# randomcontroller.net
KiCad netlist of a schematic drawn in EAGLE
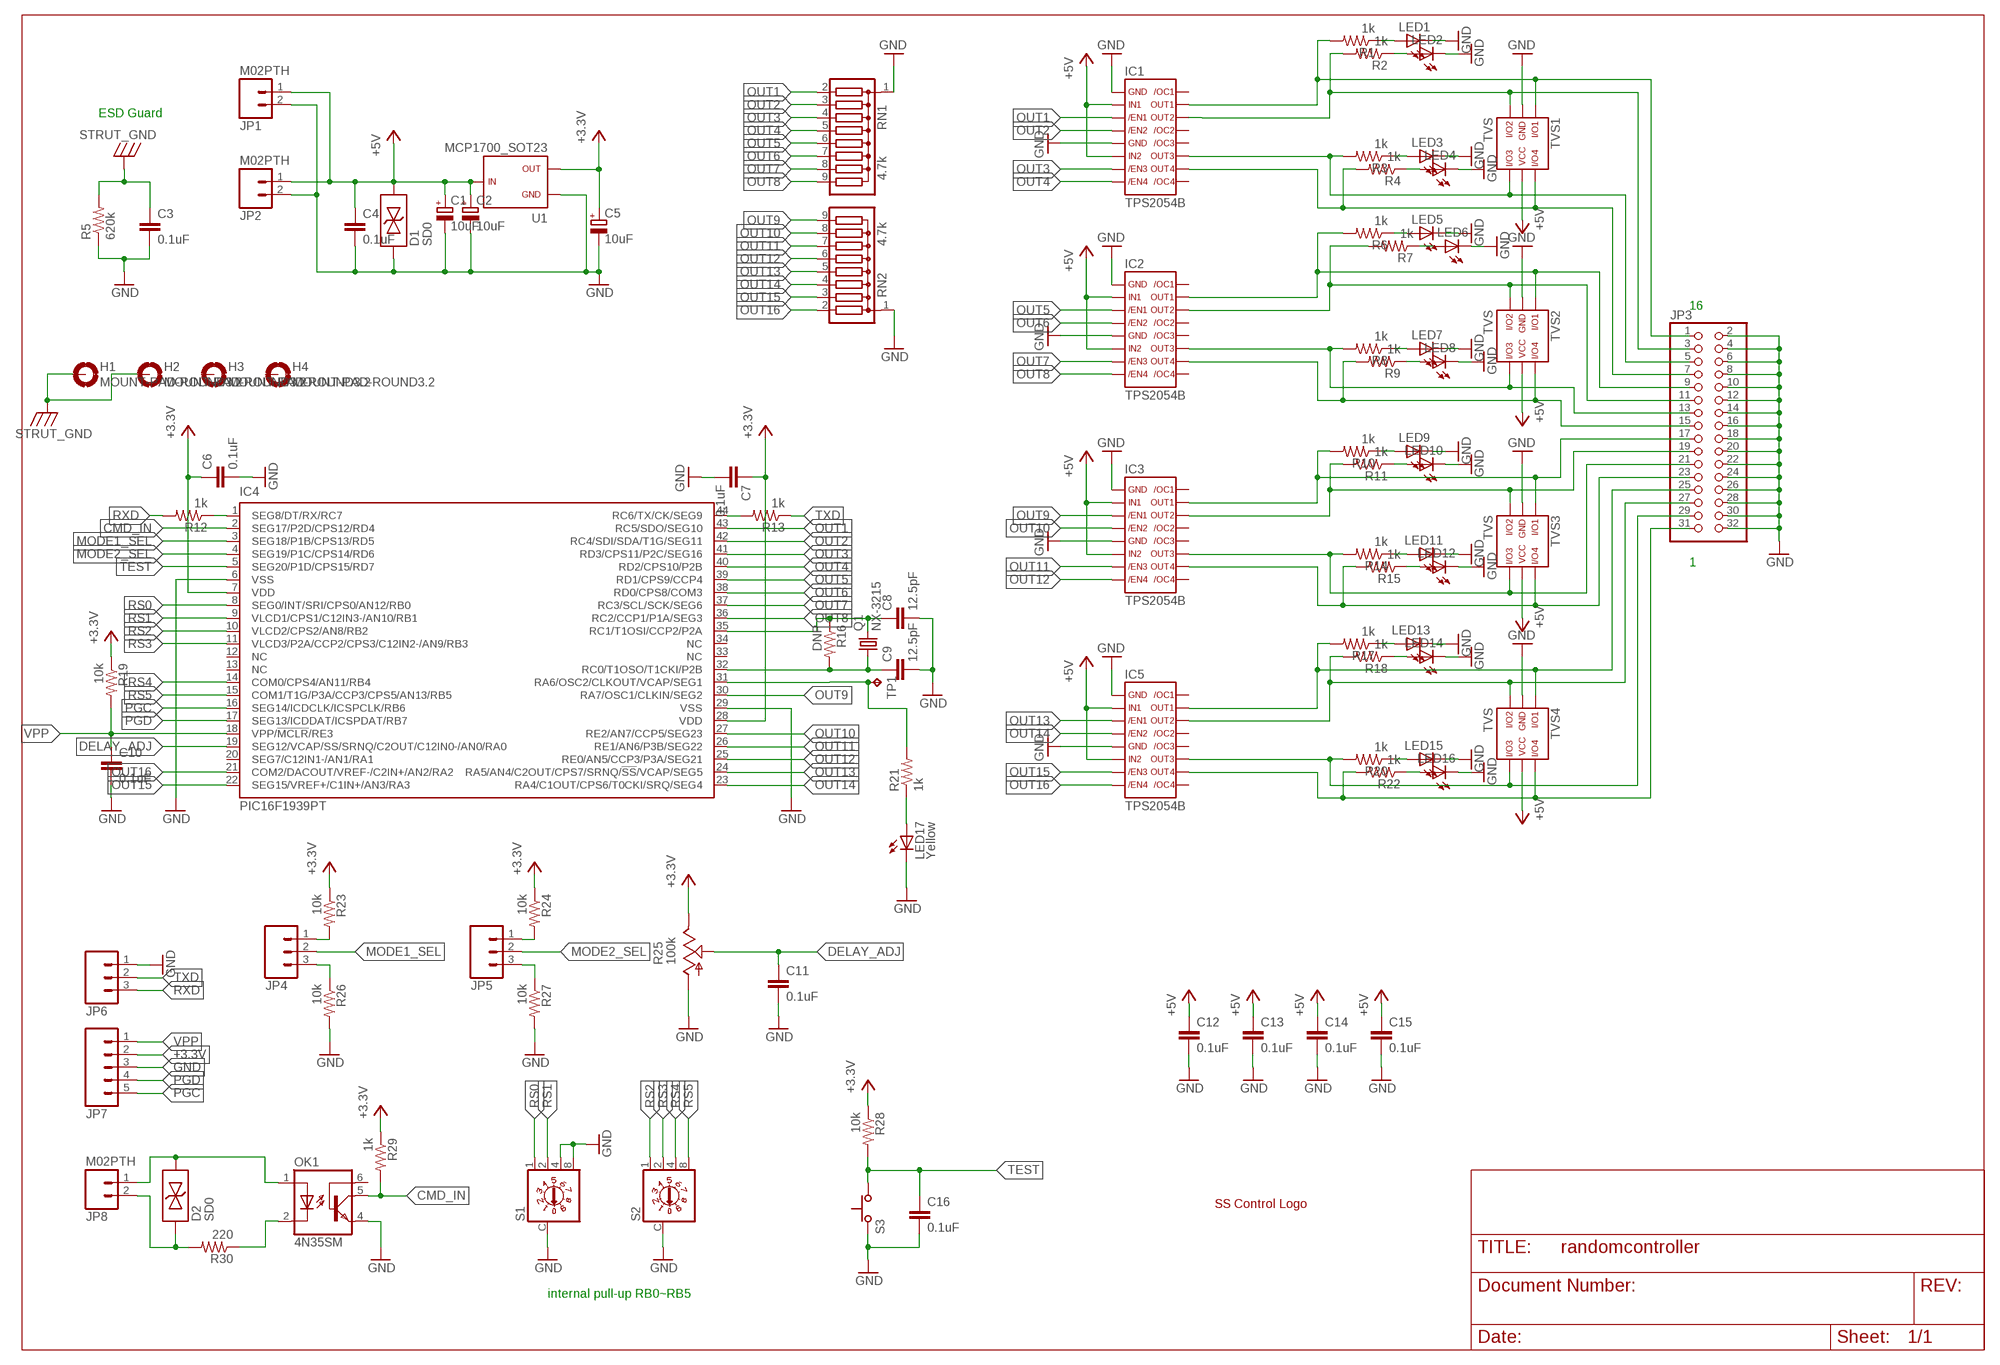
[diagram p0: schematic, sheet 1]

(export (version "E")
  (design (tool "Eeschema 10.0.6"))
  (components
    (comp (ref "C1")
      (value "10uF")
      (footprint "eagle-import:C1206(3216)-A")
      (libsource (lib "eagle-import") (part "C-TANTAL-A"))
    )
    (comp (ref "C2")
      (value "10uF")
      (footprint "eagle-import:C1206(3216)-A")
      (libsource (lib "eagle-import") (part "C-TANTAL-A"))
    )
    (comp (ref "C3")
      (value "0.1uF")
      (footprint "eagle-import:C0805(2012)")
      (libsource (lib "eagle-import") (part "C0805(2012)"))
    )
    (comp (ref "C4")
      (value "0.1uF")
      (footprint "eagle-import:C0805(2012)")
      (libsource (lib "eagle-import") (part "C0805(2012)"))
    )
    (comp (ref "C5")
      (value "10uF")
      (footprint "eagle-import:C1206(3216)-A")
      (libsource (lib "eagle-import") (part "C-TANTAL-A"))
    )
    (comp (ref "C6")
      (value "0.1uF")
      (footprint "eagle-import:C0805(2012)")
      (libsource (lib "eagle-import") (part "C0805(2012)"))
    )
    (comp (ref "C7")
      (value "0.1uF")
      (footprint "eagle-import:C0805(2012)")
      (libsource (lib "eagle-import") (part "C0805(2012)"))
    )
    (comp (ref "C8")
      (value "12.5pF")
      (footprint "eagle-import:C0805(2012)")
      (libsource (lib "eagle-import") (part "C0805(2012)"))
    )
    (comp (ref "C9")
      (value "12.5pF")
      (footprint "eagle-import:C0805(2012)")
      (libsource (lib "eagle-import") (part "C0805(2012)"))
    )
    (comp (ref "C10")
      (value "0.1uF")
      (footprint "eagle-import:C0805(2012)")
      (libsource (lib "eagle-import") (part "C0805(2012)"))
    )
    (comp (ref "C11")
      (value "0.1uF")
      (footprint "eagle-import:C0805(2012)")
      (libsource (lib "eagle-import") (part "C0805(2012)"))
    )
    (comp (ref "C12")
      (value "0.1uF")
      (footprint "eagle-import:C0805(2012)")
      (libsource (lib "eagle-import") (part "C0805(2012)"))
    )
    (comp (ref "C13")
      (value "0.1uF")
      (footprint "eagle-import:C0805(2012)")
      (libsource (lib "eagle-import") (part "C0805(2012)"))
    )
    (comp (ref "C14")
      (value "0.1uF")
      (footprint "eagle-import:C0805(2012)")
      (libsource (lib "eagle-import") (part "C0805(2012)"))
    )
    (comp (ref "C15")
      (value "0.1uF")
      (footprint "eagle-import:C0805(2012)")
      (libsource (lib "eagle-import") (part "C0805(2012)"))
    )
    (comp (ref "C16")
      (value "0.1uF")
      (footprint "eagle-import:C0805(2012)")
      (libsource (lib "eagle-import") (part "C0805(2012)"))
    )
    (comp (ref "D1")
      (value "SD0")
      (footprint "eagle-import:SOD-323")
      (libsource (lib "eagle-import") (part "SD0"))
    )
    (comp (ref "D2")
      (value "SD0")
      (footprint "eagle-import:SOD-323")
      (libsource (lib "eagle-import") (part "SD0"))
    )
    (comp (ref "H1")
      (value "MOUNT-PAD-ROUND3.2")
      (footprint "eagle-import:3,2-PAD")
      (libsource (lib "eagle-import") (part "MOUNT-PAD-ROUND3.2"))
    )
    (comp (ref "H2")
      (value "MOUNT-PAD-ROUND3.2")
      (footprint "eagle-import:3,2-PAD")
      (libsource (lib "eagle-import") (part "MOUNT-PAD-ROUND3.2"))
    )
    (comp (ref "H3")
      (value "MOUNT-PAD-ROUND3.2")
      (footprint "eagle-import:3,2-PAD")
      (libsource (lib "eagle-import") (part "MOUNT-PAD-ROUND3.2"))
    )
    (comp (ref "H4")
      (value "MOUNT-PAD-ROUND3.2")
      (footprint "eagle-import:3,2-PAD")
      (libsource (lib "eagle-import") (part "MOUNT-PAD-ROUND3.2"))
    )
    (comp (ref "IC1")
      (value "TPS2054B")
      (footprint "eagle-import:R-PDSO-G16")
      (libsource (lib "eagle-import") (part "TPS2054B"))
    )
    (comp (ref "IC2")
      (value "TPS2054B")
      (footprint "eagle-import:R-PDSO-G16")
      (libsource (lib "eagle-import") (part "TPS2054B"))
    )
    (comp (ref "IC3")
      (value "TPS2054B")
      (footprint "eagle-import:R-PDSO-G16")
      (libsource (lib "eagle-import") (part "TPS2054B"))
    )
    (comp (ref "IC4")
      (value "PIC16F1939PT")
      (footprint "eagle-import:TQFP44")
      (fields (field (name "MPN") "PIC16F1939-I/PT"))
      (libsource (lib "eagle-import") (part "PIC16F193PT9"))
    )
    (comp (ref "IC5")
      (value "TPS2054B")
      (footprint "eagle-import:R-PDSO-G16")
      (libsource (lib "eagle-import") (part "TPS2054B"))
    )
    (comp (ref "JP1")
      (value "M02PTH")
      (footprint "eagle-import:1X02")
      (libsource (lib "eagle-import") (part "M02PTH"))
    )
    (comp (ref "JP2")
      (value "M02PTH")
      (footprint "eagle-import:1X02")
      (libsource (lib "eagle-import") (part "M02PTH"))
    )
    (comp (ref "JP3")
      (value "PINHD-2X16/90")
      (footprint "eagle-import:2X16_90")
      (libsource (lib "eagle-import") (part "PINHD-2X16/90"))
    )
    (comp (ref "JP4")
      (value "M03PTH")
      (footprint "eagle-import:1X03")
      (libsource (lib "eagle-import") (part "M03PTH"))
    )
    (comp (ref "JP5")
      (value "M03PTH")
      (footprint "eagle-import:1X03")
      (libsource (lib "eagle-import") (part "M03PTH"))
    )
    (comp (ref "JP6")
      (value "M03PTH")
      (footprint "eagle-import:1X03")
      (libsource (lib "eagle-import") (part "M03PTH"))
    )
    (comp (ref "JP7")
      (value "M05PTH")
      (footprint "eagle-import:1X05")
      (libsource (lib "eagle-import") (part "M05PTH"))
    )
    (comp (ref "JP8")
      (value "M02PTH")
      (footprint "eagle-import:1X02")
      (libsource (lib "eagle-import") (part "M02PTH"))
    )
    (comp (ref "LED1")
      (value "LEDCHIPLED_0805")
      (footprint "eagle-import:CHIPLED_0805")
      (libsource (lib "eagle-import") (part "LEDCHIPLED_0805"))
    )
    (comp (ref "LED2")
      (value "LEDCHIPLED_0805")
      (footprint "eagle-import:CHIPLED_0805")
      (libsource (lib "eagle-import") (part "LEDCHIPLED_0805"))
    )
    (comp (ref "LED3")
      (value "LEDCHIPLED_0805")
      (footprint "eagle-import:CHIPLED_0805")
      (libsource (lib "eagle-import") (part "LEDCHIPLED_0805"))
    )
    (comp (ref "LED4")
      (value "LEDCHIPLED_0805")
      (footprint "eagle-import:CHIPLED_0805")
      (libsource (lib "eagle-import") (part "LEDCHIPLED_0805"))
    )
    (comp (ref "LED5")
      (value "LEDCHIPLED_0805")
      (footprint "eagle-import:CHIPLED_0805")
      (libsource (lib "eagle-import") (part "LEDCHIPLED_0805"))
    )
    (comp (ref "LED6")
      (value "LEDCHIPLED_0805")
      (footprint "eagle-import:CHIPLED_0805")
      (libsource (lib "eagle-import") (part "LEDCHIPLED_0805"))
    )
    (comp (ref "LED7")
      (value "LEDCHIPLED_0805")
      (footprint "eagle-import:CHIPLED_0805")
      (libsource (lib "eagle-import") (part "LEDCHIPLED_0805"))
    )
    (comp (ref "LED8")
      (value "LEDCHIPLED_0805")
      (footprint "eagle-import:CHIPLED_0805")
      (libsource (lib "eagle-import") (part "LEDCHIPLED_0805"))
    )
    (comp (ref "LED9")
      (value "LEDCHIPLED_0805")
      (footprint "eagle-import:CHIPLED_0805")
      (libsource (lib "eagle-import") (part "LEDCHIPLED_0805"))
    )
    (comp (ref "LED10")
      (value "LEDCHIPLED_0805")
      (footprint "eagle-import:CHIPLED_0805")
      (libsource (lib "eagle-import") (part "LEDCHIPLED_0805"))
    )
    (comp (ref "LED11")
      (value "LEDCHIPLED_0805")
      (footprint "eagle-import:CHIPLED_0805")
      (libsource (lib "eagle-import") (part "LEDCHIPLED_0805"))
    )
    (comp (ref "LED12")
      (value "LEDCHIPLED_0805")
      (footprint "eagle-import:CHIPLED_0805")
      (libsource (lib "eagle-import") (part "LEDCHIPLED_0805"))
    )
    (comp (ref "LED13")
      (value "LEDCHIPLED_0805")
      (footprint "eagle-import:CHIPLED_0805")
      (libsource (lib "eagle-import") (part "LEDCHIPLED_0805"))
    )
    (comp (ref "LED14")
      (value "LEDCHIPLED_0805")
      (footprint "eagle-import:CHIPLED_0805")
      (libsource (lib "eagle-import") (part "LEDCHIPLED_0805"))
    )
    (comp (ref "LED15")
      (value "LEDCHIPLED_0805")
      (footprint "eagle-import:CHIPLED_0805")
      (libsource (lib "eagle-import") (part "LEDCHIPLED_0805"))
    )
    (comp (ref "LED16")
      (value "LEDCHIPLED_0805")
      (footprint "eagle-import:CHIPLED_0805")
      (libsource (lib "eagle-import") (part "LEDCHIPLED_0805"))
    )
    (comp (ref "LED17")
      (value "Yellow")
      (footprint "eagle-import:CHIPLED_0805")
      (libsource (lib "eagle-import") (part "LEDCHIPLED_0805"))
    )
    (comp (ref "OK1")
      (value "4N35SM")
      (footprint "eagle-import:DIL6-SMD")
      (fields (field (name "MF") "FAIRCHILD SEMICONDUCTOR") (field (name "MPN") "4N35S-M"))
      (libsource (lib "eagle-import") (part "4N?MS35"))
    )
    (comp (ref "Q1")
      (value "NX-3215")
      (footprint "eagle-import:NX-3215")
      (libsource (lib "eagle-import") (part "NX-3215"))
    )
    (comp (ref "R1")
      (value "1k")
      (footprint "eagle-import:R0805(2012)")
      (libsource (lib "eagle-import") (part "R0805(2012)"))
    )
    (comp (ref "R2")
      (value "1k")
      (footprint "eagle-import:R0805(2012)")
      (libsource (lib "eagle-import") (part "R0805(2012)"))
    )
    (comp (ref "R3")
      (value "1k")
      (footprint "eagle-import:R0805(2012)")
      (libsource (lib "eagle-import") (part "R0805(2012)"))
    )
    (comp (ref "R4")
      (value "1k")
      (footprint "eagle-import:R0805(2012)")
      (libsource (lib "eagle-import") (part "R0805(2012)"))
    )
    (comp (ref "R5")
      (value "620k")
      (footprint "eagle-import:R0805(2012)")
      (libsource (lib "eagle-import") (part "R0805(2012)"))
    )
    (comp (ref "R6")
      (value "1k")
      (footprint "eagle-import:R0805(2012)")
      (libsource (lib "eagle-import") (part "R0805(2012)"))
    )
    (comp (ref "R7")
      (value "1k")
      (footprint "eagle-import:R0805(2012)")
      (libsource (lib "eagle-import") (part "R0805(2012)"))
    )
    (comp (ref "R8")
      (value "1k")
      (footprint "eagle-import:R0805(2012)")
      (libsource (lib "eagle-import") (part "R0805(2012)"))
    )
    (comp (ref "R9")
      (value "1k")
      (footprint "eagle-import:R0805(2012)")
      (libsource (lib "eagle-import") (part "R0805(2012)"))
    )
    (comp (ref "R10")
      (value "1k")
      (footprint "eagle-import:R0805(2012)")
      (libsource (lib "eagle-import") (part "R0805(2012)"))
    )
    (comp (ref "R11")
      (value "1k")
      (footprint "eagle-import:R0805(2012)")
      (libsource (lib "eagle-import") (part "R0805(2012)"))
    )
    (comp (ref "R12")
      (value "1k")
      (footprint "eagle-import:R0805(2012)")
      (libsource (lib "eagle-import") (part "R0805(2012)"))
    )
    (comp (ref "R13")
      (value "1k")
      (footprint "eagle-import:R0805(2012)")
      (libsource (lib "eagle-import") (part "R0805(2012)"))
    )
    (comp (ref "R14")
      (value "1k")
      (footprint "eagle-import:R0805(2012)")
      (libsource (lib "eagle-import") (part "R0805(2012)"))
    )
    (comp (ref "R15")
      (value "1k")
      (footprint "eagle-import:R0805(2012)")
      (libsource (lib "eagle-import") (part "R0805(2012)"))
    )
    (comp (ref "R16")
      (value "DNP")
      (footprint "eagle-import:R0805(2012)")
      (libsource (lib "eagle-import") (part "R0805(2012)"))
    )
    (comp (ref "R17")
      (value "1k")
      (footprint "eagle-import:R0805(2012)")
      (libsource (lib "eagle-import") (part "R0805(2012)"))
    )
    (comp (ref "R18")
      (value "1k")
      (footprint "eagle-import:R0805(2012)")
      (libsource (lib "eagle-import") (part "R0805(2012)"))
    )
    (comp (ref "R19")
      (value "10k")
      (footprint "eagle-import:R0805(2012)")
      (libsource (lib "eagle-import") (part "R0805(2012)"))
    )
    (comp (ref "R20")
      (value "1k")
      (footprint "eagle-import:R0805(2012)")
      (libsource (lib "eagle-import") (part "R0805(2012)"))
    )
    (comp (ref "R21")
      (value "1k")
      (footprint "eagle-import:R0805(2012)")
      (libsource (lib "eagle-import") (part "R0805(2012)"))
    )
    (comp (ref "R22")
      (value "1k")
      (footprint "eagle-import:R0805(2012)")
      (libsource (lib "eagle-import") (part "R0805(2012)"))
    )
    (comp (ref "R23")
      (value "10k")
      (footprint "eagle-import:R0805(2012)")
      (libsource (lib "eagle-import") (part "R0805(2012)"))
    )
    (comp (ref "R24")
      (value "10k")
      (footprint "eagle-import:R0805(2012)")
      (libsource (lib "eagle-import") (part "R0805(2012)"))
    )
    (comp (ref "R25")
      (value "100k")
      (footprint "eagle-import:B25P")
      (libsource (lib "eagle-import") (part "TRIM_US-B25P"))
    )
    (comp (ref "R26")
      (value "10k")
      (footprint "eagle-import:R0805(2012)")
      (libsource (lib "eagle-import") (part "R0805(2012)"))
    )
    (comp (ref "R27")
      (value "10k")
      (footprint "eagle-import:R0805(2012)")
      (libsource (lib "eagle-import") (part "R0805(2012)"))
    )
    (comp (ref "R28")
      (value "10k")
      (footprint "eagle-import:R0805(2012)")
      (libsource (lib "eagle-import") (part "R0805(2012)"))
    )
    (comp (ref "R29")
      (value "1k")
      (footprint "eagle-import:R0805(2012)")
      (libsource (lib "eagle-import") (part "R0805(2012)"))
    )
    (comp (ref "R30")
      (value "220")
      (footprint "eagle-import:R0805(2012)")
      (libsource (lib "eagle-import") (part "R0805(2012)"))
    )
    (comp (ref "RN1")
      (value "4.7k")
      (footprint "eagle-import:SIL9")
      (libsource (lib "eagle-import") (part "G08R"))
    )
    (comp (ref "RN2")
      (value "4.7k")
      (footprint "eagle-import:SIL9")
      (libsource (lib "eagle-import") (part "G08R"))
    )
    (comp (ref "S1")
      (value "S20BCD")
      (footprint "eagle-import:S20BCD")
      (libsource (lib "eagle-import") (part "S20BCD"))
    )
    (comp (ref "S2")
      (value "S20BCD")
      (footprint "eagle-import:S20BCD")
      (libsource (lib "eagle-import") (part "S20BCD"))
    )
    (comp (ref "S3")
      (value "SWITCH")
      (footprint "eagle-import:SKHLACA010")
      (libsource (lib "eagle-import") (part "SWITCH"))
    )
    (comp (ref "TP1")
      (value "TP")
      (footprint "eagle-import:TP-13")
      (libsource (lib "eagle-import") (part "TP"))
    )
    (comp (ref "TVS1")
      (value "TVS")
      (footprint "eagle-import:TSOP-6")
      (libsource (lib "eagle-import") (part "TVS"))
    )
    (comp (ref "TVS2")
      (value "TVS")
      (footprint "eagle-import:TSOP-6")
      (libsource (lib "eagle-import") (part "TVS"))
    )
    (comp (ref "TVS3")
      (value "TVS")
      (footprint "eagle-import:TSOP-6")
      (libsource (lib "eagle-import") (part "TVS"))
    )
    (comp (ref "TVS4")
      (value "TVS")
      (footprint "eagle-import:TSOP-6")
      (libsource (lib "eagle-import") (part "TVS"))
    )
    (comp (ref "U$1")
      (value "LOGO")
      (footprint "eagle-import:SSCONTROL")
      (libsource (lib "eagle-import") (part "LOGO"))
    )
    (comp (ref "U1")
      (value "MCP1700_SOT23")
      (footprint "eagle-import:SOT23")
      (libsource (lib "eagle-import") (part "MCP1700_SOT23"))
    )
  )
  (nets
    (net (code "1") (name "+3.3V") (class "Default")
      (node (ref "C5") (pin "1") (pinfunction "+_1") (pintype "passive"))
      (node (ref "C6") (pin "1") (pinfunction "1_1") (pintype "passive"))
      (node (ref "C7") (pin "1") (pinfunction "1_1") (pintype "passive"))
      (node (ref "IC4") (pin "28") (pinfunction "VDD_28") (pintype "power_in"))
      (node (ref "IC4") (pin "7") (pinfunction "VDD_7") (pintype "power_in"))
      (node (ref "JP7") (pin "2") (pinfunction "2_2") (pintype "passive"))
      (node (ref "R19") (pin "1") (pinfunction "1_1") (pintype "passive"))
      (node (ref "R23") (pin "1") (pinfunction "1_1") (pintype "passive"))
      (node (ref "R24") (pin "1") (pinfunction "1_1") (pintype "passive"))
      (node (ref "R25") (pin "E") (pinfunction "E_E") (pintype "passive"))
      (node (ref "R28") (pin "1") (pinfunction "1_1") (pintype "passive"))
      (node (ref "R29") (pin "1") (pinfunction "1_1") (pintype "passive"))
      (node (ref "U1") (pin "2") (pinfunction "2_2") (pintype "power_in"))
    )
    (net (code "2") (name "+5V") (class "Default")
      (node (ref "C1") (pin "1") (pinfunction "+_1") (pintype "passive"))
      (node (ref "C12") (pin "1") (pinfunction "1_1") (pintype "passive"))
      (node (ref "C13") (pin "1") (pinfunction "1_1") (pintype "passive"))
      (node (ref "C14") (pin "1") (pinfunction "1_1") (pintype "passive"))
      (node (ref "C15") (pin "1") (pinfunction "1_1") (pintype "passive"))
      (node (ref "C2") (pin "1") (pinfunction "+_1") (pintype "passive"))
      (node (ref "C4") (pin "1") (pinfunction "1_1") (pintype "passive"))
      (node (ref "D1") (pin "2") (pinfunction "P$2_2") (pintype "bidirectional"))
      (node (ref "IC1") (pin "2") (pinfunction "P$2_2") (pintype "input"))
      (node (ref "IC1") (pin "6") (pinfunction "P$6_6") (pintype "input"))
      (node (ref "IC2") (pin "2") (pinfunction "P$2_2") (pintype "input"))
      (node (ref "IC2") (pin "6") (pinfunction "P$6_6") (pintype "input"))
      (node (ref "IC3") (pin "2") (pinfunction "P$2_2") (pintype "input"))
      (node (ref "IC3") (pin "6") (pinfunction "P$6_6") (pintype "input"))
      (node (ref "IC5") (pin "2") (pinfunction "P$2_2") (pintype "input"))
      (node (ref "IC5") (pin "6") (pinfunction "P$6_6") (pintype "input"))
      (node (ref "JP1") (pin "1") (pinfunction "1_1") (pintype "passive"))
      (node (ref "JP2") (pin "1") (pinfunction "1_1") (pintype "passive"))
      (node (ref "TVS1") (pin "5") (pinfunction "P$5_5") (pintype "bidirectional"))
      (node (ref "TVS2") (pin "5") (pinfunction "P$5_5") (pintype "bidirectional"))
      (node (ref "TVS3") (pin "5") (pinfunction "P$5_5") (pintype "bidirectional"))
      (node (ref "TVS4") (pin "5") (pinfunction "P$5_5") (pintype "bidirectional"))
      (node (ref "U1") (pin "3") (pinfunction "3_3") (pintype "power_in"))
    )
    (net (code "3") (name "CMD_IN") (class "Default")
      (node (ref "IC4") (pin "2") (pinfunction "SEG17/P2D/CPS12/RD4_2") (pintype "bidirectional"))
      (node (ref "OK1") (pin "5") (pinfunction "COL_5") (pintype "passive"))
      (node (ref "R29") (pin "2") (pinfunction "2_2") (pintype "passive"))
    )
    (net (code "4") (name "DELAY_ADJ") (class "Default")
      (node (ref "C11") (pin "1") (pinfunction "1_1") (pintype "passive"))
      (node (ref "IC4") (pin "19") (pinfunction "SEG12/VCAP/SS/SRNQ/C2OUT/C12IN0-/AN0/RA0_19") (pintype "bidirectional"))
      (node (ref "R25") (pin "S") (pinfunction "S_S") (pintype "passive"))
    )
    (net (code "5") (name "GND") (class "Default")
      (node (ref "C1") (pin "2") (pinfunction "-_2") (pintype "passive"))
      (node (ref "C10") (pin "2") (pinfunction "2_2") (pintype "passive"))
      (node (ref "C11") (pin "2") (pinfunction "2_2") (pintype "passive"))
      (node (ref "C12") (pin "2") (pinfunction "2_2") (pintype "passive"))
      (node (ref "C13") (pin "2") (pinfunction "2_2") (pintype "passive"))
      (node (ref "C14") (pin "2") (pinfunction "2_2") (pintype "passive"))
      (node (ref "C15") (pin "2") (pinfunction "2_2") (pintype "passive"))
      (node (ref "C16") (pin "2") (pinfunction "2_2") (pintype "passive"))
      (node (ref "C2") (pin "2") (pinfunction "-_2") (pintype "passive"))
      (node (ref "C3") (pin "2") (pinfunction "2_2") (pintype "passive"))
      (node (ref "C4") (pin "2") (pinfunction "2_2") (pintype "passive"))
      (node (ref "C5") (pin "2") (pinfunction "-_2") (pintype "passive"))
      (node (ref "C6") (pin "2") (pinfunction "2_2") (pintype "passive"))
      (node (ref "C7") (pin "2") (pinfunction "2_2") (pintype "passive"))
      (node (ref "C8") (pin "2") (pinfunction "2_2") (pintype "passive"))
      (node (ref "C9") (pin "2") (pinfunction "2_2") (pintype "passive"))
      (node (ref "D1") (pin "1") (pinfunction "P$1_1") (pintype "bidirectional"))
      (node (ref "IC1") (pin "1") (pinfunction "P$1_1") (pintype "power_in"))
      (node (ref "IC1") (pin "5") (pinfunction "P$5_5") (pintype "power_in"))
      (node (ref "IC2") (pin "1") (pinfunction "P$1_1") (pintype "power_in"))
      (node (ref "IC2") (pin "5") (pinfunction "P$5_5") (pintype "power_in"))
      (node (ref "IC3") (pin "1") (pinfunction "P$1_1") (pintype "power_in"))
      (node (ref "IC3") (pin "5") (pinfunction "P$5_5") (pintype "power_in"))
      (node (ref "IC4") (pin "29") (pinfunction "VSS_29") (pintype "power_in"))
      (node (ref "IC4") (pin "6") (pinfunction "VSS_6") (pintype "power_in"))
      (node (ref "IC5") (pin "1") (pinfunction "P$1_1") (pintype "power_in"))
      (node (ref "IC5") (pin "5") (pinfunction "P$5_5") (pintype "power_in"))
      (node (ref "JP1") (pin "2") (pinfunction "2_2") (pintype "passive"))
      (node (ref "JP2") (pin "2") (pinfunction "2_2") (pintype "passive"))
      (node (ref "JP3") (pin "10") (pinfunction "10_10") (pintype "passive"))
      (node (ref "JP3") (pin "12") (pinfunction "12_12") (pintype "passive"))
      (node (ref "JP3") (pin "14") (pinfunction "14_14") (pintype "passive"))
      (node (ref "JP3") (pin "16") (pinfunction "16_16") (pintype "passive"))
      (node (ref "JP3") (pin "18") (pinfunction "18_18") (pintype "passive"))
      (node (ref "JP3") (pin "2") (pinfunction "2_2") (pintype "passive"))
      (node (ref "JP3") (pin "20") (pinfunction "20_20") (pintype "passive"))
      (node (ref "JP3") (pin "22") (pinfunction "22_22") (pintype "passive"))
      (node (ref "JP3") (pin "24") (pinfunction "24_24") (pintype "passive"))
      (node (ref "JP3") (pin "26") (pinfunction "26_26") (pintype "passive"))
      (node (ref "JP3") (pin "28") (pinfunction "28_28") (pintype "passive"))
      (node (ref "JP3") (pin "30") (pinfunction "30_30") (pintype "passive"))
      (node (ref "JP3") (pin "32") (pinfunction "32_32") (pintype "passive"))
      (node (ref "JP3") (pin "4") (pinfunction "4_4") (pintype "passive"))
      (node (ref "JP3") (pin "6") (pinfunction "6_6") (pintype "passive"))
      (node (ref "JP3") (pin "8") (pinfunction "8_8") (pintype "passive"))
      (node (ref "JP6") (pin "1") (pinfunction "1_1") (pintype "passive"))
      (node (ref "JP7") (pin "3") (pinfunction "3_3") (pintype "passive"))
      (node (ref "LED1") (pin "C") (pinfunction "C_C") (pintype "passive"))
      (node (ref "LED10") (pin "C") (pinfunction "C_C") (pintype "passive"))
      (node (ref "LED11") (pin "C") (pinfunction "C_C") (pintype "passive"))
      (node (ref "LED12") (pin "C") (pinfunction "C_C") (pintype "passive"))
      (node (ref "LED13") (pin "C") (pinfunction "C_C") (pintype "passive"))
      (node (ref "LED14") (pin "C") (pinfunction "C_C") (pintype "passive"))
      (node (ref "LED15") (pin "C") (pinfunction "C_C") (pintype "passive"))
      (node (ref "LED16") (pin "C") (pinfunction "C_C") (pintype "passive"))
      (node (ref "LED17") (pin "C") (pinfunction "C_C") (pintype "passive"))
      (node (ref "LED2") (pin "C") (pinfunction "C_C") (pintype "passive"))
      (node (ref "LED3") (pin "C") (pinfunction "C_C") (pintype "passive"))
      (node (ref "LED4") (pin "C") (pinfunction "C_C") (pintype "passive"))
      (node (ref "LED5") (pin "C") (pinfunction "C_C") (pintype "passive"))
      (node (ref "LED6") (pin "C") (pinfunction "C_C") (pintype "passive"))
      (node (ref "LED7") (pin "C") (pinfunction "C_C") (pintype "passive"))
      (node (ref "LED8") (pin "C") (pinfunction "C_C") (pintype "passive"))
      (node (ref "LED9") (pin "C") (pinfunction "C_C") (pintype "passive"))
      (node (ref "OK1") (pin "4") (pinfunction "EMI_4") (pintype "passive"))
      (node (ref "R25") (pin "A") (pinfunction "A_A") (pintype "passive"))
      (node (ref "R26") (pin "2") (pinfunction "2_2") (pintype "passive"))
      (node (ref "R27") (pin "2") (pinfunction "2_2") (pintype "passive"))
      (node (ref "R5") (pin "1") (pinfunction "1_1") (pintype "passive"))
      (node (ref "RN1") (pin "1") (pinfunction "1_1") (pintype "passive"))
      (node (ref "RN2") (pin "1") (pinfunction "1_1") (pintype "passive"))
      (node (ref "S1") (pin "4") (pinfunction "4_4") (pintype "passive"))
      (node (ref "S1") (pin "8") (pinfunction "8_8") (pintype "passive"))
      (node (ref "S1") (pin "C") (pinfunction "C_C") (pintype "passive"))
      (node (ref "S2") (pin "C") (pinfunction "C_C") (pintype "passive"))
      (node (ref "S3") (pin "P$1") (pinfunction "P$1_P$1") (pintype "bidirectional"))
      (node (ref "TVS1") (pin "2") (pinfunction "P$2_2") (pintype "bidirectional"))
      (node (ref "TVS2") (pin "2") (pinfunction "P$2_2") (pintype "bidirectional"))
      (node (ref "TVS3") (pin "2") (pinfunction "P$2_2") (pintype "bidirectional"))
      (node (ref "TVS4") (pin "2") (pinfunction "P$2_2") (pintype "bidirectional"))
      (node (ref "U1") (pin "1") (pinfunction "1_1") (pintype "power_in"))
    )
    (net (code "6") (name "MODE1_SEL") (class "Default")
      (node (ref "IC4") (pin "3") (pinfunction "SEG18/P1B/CPS13/RD5_3") (pintype "bidirectional"))
      (node (ref "JP4") (pin "2") (pinfunction "2_2") (pintype "passive"))
    )
    (net (code "7") (name "MODE2_SEL") (class "Default")
      (node (ref "IC4") (pin "4") (pinfunction "SEG19/P1C/CPS14/RD6_4") (pintype "bidirectional"))
      (node (ref "JP5") (pin "2") (pinfunction "2_2") (pintype "passive"))
    )
    (net (code "8") (name "Net-(D2-P$1)") (class "Default")
      (node (ref "D2") (pin "1") (pinfunction "P$1_1") (pintype "bidirectional"))
      (node (ref "JP8") (pin "2") (pinfunction "2_2") (pintype "passive"))
      (node (ref "R30") (pin "2") (pinfunction "2_2") (pintype "passive"))
    )
    (net (code "9") (name "Net-(D2-P$2)") (class "Default")
      (node (ref "D2") (pin "2") (pinfunction "P$2_2") (pintype "bidirectional"))
      (node (ref "JP8") (pin "1") (pinfunction "1_1") (pintype "passive"))
      (node (ref "OK1") (pin "1") (pinfunction "A_1") (pintype "passive"))
    )
    (net (code "10") (name "Net-(IC1-P$10)") (class "Default")
      (node (ref "IC1") (pin "10") (pinfunction "P$10_10") (pintype "output"))
      (node (ref "JP3") (pin "7") (pinfunction "7_7") (pintype "passive"))
      (node (ref "R4") (pin "2") (pinfunction "2_2") (pintype "passive"))
      (node (ref "TVS1") (pin "6") (pinfunction "P$6_6") (pintype "bidirectional"))
    )
    (net (code "11") (name "Net-(IC1-P$11)") (class "Default")
      (node (ref "IC1") (pin "11") (pinfunction "P$11_11") (pintype "output"))
      (node (ref "JP3") (pin "5") (pinfunction "5_5") (pintype "passive"))
      (node (ref "R3") (pin "2") (pinfunction "2_2") (pintype "passive"))
      (node (ref "TVS1") (pin "4") (pinfunction "P$4_4") (pintype "bidirectional"))
    )
    (net (code "12") (name "Net-(IC1-P$14)") (class "Default")
      (node (ref "IC1") (pin "14") (pinfunction "P$14_14") (pintype "output"))
      (node (ref "JP3") (pin "3") (pinfunction "3_3") (pintype "passive"))
      (node (ref "R2") (pin "2") (pinfunction "2_2") (pintype "passive"))
      (node (ref "TVS1") (pin "3") (pinfunction "P$3_3") (pintype "bidirectional"))
    )
    (net (code "13") (name "Net-(IC1-P$15)") (class "Default")
      (node (ref "IC1") (pin "15") (pinfunction "P$15_15") (pintype "output"))
      (node (ref "JP3") (pin "1") (pinfunction "1_1") (pintype "passive"))
      (node (ref "R1") (pin "2") (pinfunction "2_2") (pintype "passive"))
      (node (ref "TVS1") (pin "1") (pinfunction "P$1_1") (pintype "bidirectional"))
    )
    (net (code "14") (name "Net-(IC2-P$10)") (class "Default")
      (node (ref "IC2") (pin "10") (pinfunction "P$10_10") (pintype "output"))
      (node (ref "JP3") (pin "15") (pinfunction "15_15") (pintype "passive"))
      (node (ref "R9") (pin "2") (pinfunction "2_2") (pintype "passive"))
      (node (ref "TVS2") (pin "6") (pinfunction "P$6_6") (pintype "bidirectional"))
    )
    (net (code "15") (name "Net-(IC2-P$11)") (class "Default")
      (node (ref "IC2") (pin "11") (pinfunction "P$11_11") (pintype "output"))
      (node (ref "JP3") (pin "13") (pinfunction "13_13") (pintype "passive"))
      (node (ref "R8") (pin "2") (pinfunction "2_2") (pintype "passive"))
      (node (ref "TVS2") (pin "4") (pinfunction "P$4_4") (pintype "bidirectional"))
    )
    (net (code "16") (name "Net-(IC2-P$14)") (class "Default")
      (node (ref "IC2") (pin "14") (pinfunction "P$14_14") (pintype "output"))
      (node (ref "JP3") (pin "11") (pinfunction "11_11") (pintype "passive"))
      (node (ref "R7") (pin "2") (pinfunction "2_2") (pintype "passive"))
      (node (ref "TVS2") (pin "3") (pinfunction "P$3_3") (pintype "bidirectional"))
    )
    (net (code "17") (name "Net-(IC2-P$15)") (class "Default")
      (node (ref "IC2") (pin "15") (pinfunction "P$15_15") (pintype "output"))
      (node (ref "JP3") (pin "9") (pinfunction "9_9") (pintype "passive"))
      (node (ref "R6") (pin "2") (pinfunction "2_2") (pintype "passive"))
      (node (ref "TVS2") (pin "1") (pinfunction "P$1_1") (pintype "bidirectional"))
    )
    (net (code "18") (name "Net-(IC3-P$10)") (class "Default")
      (node (ref "IC3") (pin "10") (pinfunction "P$10_10") (pintype "output"))
      (node (ref "JP3") (pin "23") (pinfunction "23_23") (pintype "passive"))
      (node (ref "R15") (pin "2") (pinfunction "2_2") (pintype "passive"))
      (node (ref "TVS3") (pin "6") (pinfunction "P$6_6") (pintype "bidirectional"))
    )
    (net (code "19") (name "Net-(IC3-P$11)") (class "Default")
      (node (ref "IC3") (pin "11") (pinfunction "P$11_11") (pintype "output"))
      (node (ref "JP3") (pin "21") (pinfunction "21_21") (pintype "passive"))
      (node (ref "R14") (pin "2") (pinfunction "2_2") (pintype "passive"))
      (node (ref "TVS3") (pin "4") (pinfunction "P$4_4") (pintype "bidirectional"))
    )
    (net (code "20") (name "Net-(IC3-P$14)") (class "Default")
      (node (ref "IC3") (pin "14") (pinfunction "P$14_14") (pintype "output"))
      (node (ref "JP3") (pin "19") (pinfunction "19_19") (pintype "passive"))
      (node (ref "R11") (pin "2") (pinfunction "2_2") (pintype "passive"))
      (node (ref "TVS3") (pin "3") (pinfunction "P$3_3") (pintype "bidirectional"))
    )
    (net (code "21") (name "Net-(IC3-P$15)") (class "Default")
      (node (ref "IC3") (pin "15") (pinfunction "P$15_15") (pintype "output"))
      (node (ref "JP3") (pin "17") (pinfunction "17_17") (pintype "passive"))
      (node (ref "R10") (pin "2") (pinfunction "2_2") (pintype "passive"))
      (node (ref "TVS3") (pin "1") (pinfunction "P$1_1") (pintype "bidirectional"))
    )
    (net (code "22") (name "Net-(IC4-RA6{slash}OSC2{slash}CLKOUT{slash}VCAP{slash}SEG1)") (class "Default")
      (node (ref "IC4") (pin "31") (pinfunction "RA6/OSC2/CLKOUT/VCAP/SEG1_31") (pintype "bidirectional"))
      (node (ref "R21") (pin "2") (pinfunction "2_2") (pintype "passive"))
      (node (ref "TP1") (pin "TP") (pinfunction "TP_TP") (pintype "input"))
    )
    (net (code "23") (name "Net-(IC4-RC0{slash}T1OSO{slash}T1CKI{slash}P2B)") (class "Default")
      (node (ref "C9") (pin "1") (pinfunction "1_1") (pintype "passive"))
      (node (ref "IC4") (pin "32") (pinfunction "RC0/T1OSO/T1CKI/P2B_32") (pintype "bidirectional"))
      (node (ref "Q1") (pin "1") (pinfunction "1_1") (pintype "passive"))
      (node (ref "R16") (pin "2") (pinfunction "2_2") (pintype "passive"))
    )
    (net (code "24") (name "Net-(IC4-RC1{slash}T1OSI{slash}CCP2{slash}P2A)") (class "Default")
      (node (ref "C8") (pin "1") (pinfunction "1_1") (pintype "passive"))
      (node (ref "IC4") (pin "35") (pinfunction "RC1/T1OSI/CCP2/P2A_35") (pintype "bidirectional"))
      (node (ref "Q1") (pin "2") (pinfunction "2_2") (pintype "passive"))
      (node (ref "R16") (pin "1") (pinfunction "1_1") (pintype "passive"))
    )
    (net (code "25") (name "Net-(IC4-RC6{slash}TX{slash}CK{slash}SEG9)") (class "Default")
      (node (ref "IC4") (pin "44") (pinfunction "RC6/TX/CK/SEG9_44") (pintype "bidirectional"))
      (node (ref "R13") (pin "2") (pinfunction "2_2") (pintype "passive"))
    )
    (net (code "26") (name "Net-(IC4-SEG8{slash}DT{slash}RX{slash}RC7)") (class "Default")
      (node (ref "IC4") (pin "1") (pinfunction "SEG8/DT/RX/RC7_1") (pintype "bidirectional"))
      (node (ref "R12") (pin "1") (pinfunction "1_1") (pintype "passive"))
    )
    (net (code "27") (name "Net-(IC5-P$10)") (class "Default")
      (node (ref "IC5") (pin "10") (pinfunction "P$10_10") (pintype "output"))
      (node (ref "JP3") (pin "31") (pinfunction "31_31") (pintype "passive"))
      (node (ref "R22") (pin "2") (pinfunction "2_2") (pintype "passive"))
      (node (ref "TVS4") (pin "6") (pinfunction "P$6_6") (pintype "bidirectional"))
    )
    (net (code "28") (name "Net-(IC5-P$11)") (class "Default")
      (node (ref "IC5") (pin "11") (pinfunction "P$11_11") (pintype "output"))
      (node (ref "JP3") (pin "29") (pinfunction "29_29") (pintype "passive"))
      (node (ref "R20") (pin "2") (pinfunction "2_2") (pintype "passive"))
      (node (ref "TVS4") (pin "4") (pinfunction "P$4_4") (pintype "bidirectional"))
    )
    (net (code "29") (name "Net-(IC5-P$14)") (class "Default")
      (node (ref "IC5") (pin "14") (pinfunction "P$14_14") (pintype "output"))
      (node (ref "JP3") (pin "27") (pinfunction "27_27") (pintype "passive"))
      (node (ref "R18") (pin "2") (pinfunction "2_2") (pintype "passive"))
      (node (ref "TVS4") (pin "3") (pinfunction "P$3_3") (pintype "bidirectional"))
    )
    (net (code "30") (name "Net-(IC5-P$15)") (class "Default")
      (node (ref "IC5") (pin "15") (pinfunction "P$15_15") (pintype "output"))
      (node (ref "JP3") (pin "25") (pinfunction "25_25") (pintype "passive"))
      (node (ref "R17") (pin "2") (pinfunction "2_2") (pintype "passive"))
      (node (ref "TVS4") (pin "1") (pinfunction "P$1_1") (pintype "bidirectional"))
    )
    (net (code "31") (name "Net-(JP4-Pad1)") (class "Default")
      (node (ref "JP4") (pin "1") (pinfunction "1_1") (pintype "passive"))
      (node (ref "R23") (pin "2") (pinfunction "2_2") (pintype "passive"))
    )
    (net (code "32") (name "Net-(JP4-Pad3)") (class "Default")
      (node (ref "JP4") (pin "3") (pinfunction "3_3") (pintype "passive"))
      (node (ref "R26") (pin "1") (pinfunction "1_1") (pintype "passive"))
    )
    (net (code "33") (name "Net-(JP5-Pad1)") (class "Default")
      (node (ref "JP5") (pin "1") (pinfunction "1_1") (pintype "passive"))
      (node (ref "R24") (pin "2") (pinfunction "2_2") (pintype "passive"))
    )
    (net (code "34") (name "Net-(JP5-Pad3)") (class "Default")
      (node (ref "JP5") (pin "3") (pinfunction "3_3") (pintype "passive"))
      (node (ref "R27") (pin "1") (pinfunction "1_1") (pintype "passive"))
    )
    (net (code "35") (name "Net-(LED1-PadA)") (class "Default")
      (node (ref "LED1") (pin "A") (pinfunction "A_A") (pintype "passive"))
      (node (ref "R1") (pin "1") (pinfunction "1_1") (pintype "passive"))
    )
    (net (code "36") (name "Net-(LED2-PadA)") (class "Default")
      (node (ref "LED2") (pin "A") (pinfunction "A_A") (pintype "passive"))
      (node (ref "R2") (pin "1") (pinfunction "1_1") (pintype "passive"))
    )
    (net (code "37") (name "Net-(LED3-PadA)") (class "Default")
      (node (ref "LED3") (pin "A") (pinfunction "A_A") (pintype "passive"))
      (node (ref "R3") (pin "1") (pinfunction "1_1") (pintype "passive"))
    )
    (net (code "38") (name "Net-(LED4-PadA)") (class "Default")
      (node (ref "LED4") (pin "A") (pinfunction "A_A") (pintype "passive"))
      (node (ref "R4") (pin "1") (pinfunction "1_1") (pintype "passive"))
    )
    (net (code "39") (name "Net-(LED5-PadA)") (class "Default")
      (node (ref "LED5") (pin "A") (pinfunction "A_A") (pintype "passive"))
      (node (ref "R6") (pin "1") (pinfunction "1_1") (pintype "passive"))
    )
    (net (code "40") (name "Net-(LED6-PadA)") (class "Default")
      (node (ref "LED6") (pin "A") (pinfunction "A_A") (pintype "passive"))
      (node (ref "R7") (pin "1") (pinfunction "1_1") (pintype "passive"))
    )
    (net (code "41") (name "Net-(LED7-PadA)") (class "Default")
      (node (ref "LED7") (pin "A") (pinfunction "A_A") (pintype "passive"))
      (node (ref "R8") (pin "1") (pinfunction "1_1") (pintype "passive"))
    )
    (net (code "42") (name "Net-(LED8-PadA)") (class "Default")
      (node (ref "LED8") (pin "A") (pinfunction "A_A") (pintype "passive"))
      (node (ref "R9") (pin "1") (pinfunction "1_1") (pintype "passive"))
    )
    (net (code "43") (name "Net-(LED9-PadA)") (class "Default")
      (node (ref "LED9") (pin "A") (pinfunction "A_A") (pintype "passive"))
      (node (ref "R10") (pin "1") (pinfunction "1_1") (pintype "passive"))
    )
    (net (code "44") (name "Net-(LED10-PadA)") (class "Default")
      (node (ref "LED10") (pin "A") (pinfunction "A_A") (pintype "passive"))
      (node (ref "R11") (pin "1") (pinfunction "1_1") (pintype "passive"))
    )
    (net (code "45") (name "Net-(LED11-PadA)") (class "Default")
      (node (ref "LED11") (pin "A") (pinfunction "A_A") (pintype "passive"))
      (node (ref "R14") (pin "1") (pinfunction "1_1") (pintype "passive"))
    )
    (net (code "46") (name "Net-(LED12-PadA)") (class "Default")
      (node (ref "LED12") (pin "A") (pinfunction "A_A") (pintype "passive"))
      (node (ref "R15") (pin "1") (pinfunction "1_1") (pintype "passive"))
    )
    (net (code "47") (name "Net-(LED13-PadA)") (class "Default")
      (node (ref "LED13") (pin "A") (pinfunction "A_A") (pintype "passive"))
      (node (ref "R17") (pin "1") (pinfunction "1_1") (pintype "passive"))
    )
    (net (code "48") (name "Net-(LED14-PadA)") (class "Default")
      (node (ref "LED14") (pin "A") (pinfunction "A_A") (pintype "passive"))
      (node (ref "R18") (pin "1") (pinfunction "1_1") (pintype "passive"))
    )
    (net (code "49") (name "Net-(LED15-PadA)") (class "Default")
      (node (ref "LED15") (pin "A") (pinfunction "A_A") (pintype "passive"))
      (node (ref "R20") (pin "1") (pinfunction "1_1") (pintype "passive"))
    )
    (net (code "50") (name "Net-(LED16-PadA)") (class "Default")
      (node (ref "LED16") (pin "A") (pinfunction "A_A") (pintype "passive"))
      (node (ref "R22") (pin "1") (pinfunction "1_1") (pintype "passive"))
    )
    (net (code "51") (name "Net-(LED17-PadA)") (class "Default")
      (node (ref "LED17") (pin "A") (pinfunction "A_A") (pintype "passive"))
      (node (ref "R21") (pin "1") (pinfunction "1_1") (pintype "passive"))
    )
    (net (code "52") (name "Net-(OK1-C)") (class "Default")
      (node (ref "OK1") (pin "2") (pinfunction "C_2") (pintype "passive"))
      (node (ref "R30") (pin "1") (pinfunction "1_1") (pintype "passive"))
    )
    (net (code "53") (name "OUT1") (class "Default")
      (node (ref "IC1") (pin "3") (pinfunction "P$3_3") (pintype "input"))
      (node (ref "IC4") (pin "43") (pinfunction "RC5/SDO/SEG10_43") (pintype "bidirectional"))
      (node (ref "RN1") (pin "2") (pinfunction "2_2") (pintype "passive"))
    )
    (net (code "54") (name "OUT2") (class "Default")
      (node (ref "IC1") (pin "4") (pinfunction "P$4_4") (pintype "input"))
      (node (ref "IC4") (pin "42") (pinfunction "RC4/SDI/SDA/T1G/SEG11_42") (pintype "bidirectional"))
      (node (ref "RN1") (pin "3") (pinfunction "3_3") (pintype "passive"))
    )
    (net (code "55") (name "OUT3") (class "Default")
      (node (ref "IC1") (pin "7") (pinfunction "P$7_7") (pintype "input"))
      (node (ref "IC4") (pin "41") (pinfunction "RD3/CPS11/P2C/SEG16_41") (pintype "bidirectional"))
      (node (ref "RN1") (pin "4") (pinfunction "4_4") (pintype "passive"))
    )
    (net (code "56") (name "OUT4") (class "Default")
      (node (ref "IC1") (pin "8") (pinfunction "P$8_8") (pintype "input"))
      (node (ref "IC4") (pin "40") (pinfunction "RD2/CPS10/P2B_40") (pintype "bidirectional"))
      (node (ref "RN1") (pin "5") (pinfunction "5_5") (pintype "passive"))
    )
    (net (code "57") (name "OUT5") (class "Default")
      (node (ref "IC2") (pin "3") (pinfunction "P$3_3") (pintype "input"))
      (node (ref "IC4") (pin "39") (pinfunction "RD1/CPS9/CCP4_39") (pintype "bidirectional"))
      (node (ref "RN1") (pin "6") (pinfunction "6_6") (pintype "passive"))
    )
    (net (code "58") (name "OUT6") (class "Default")
      (node (ref "IC2") (pin "4") (pinfunction "P$4_4") (pintype "input"))
      (node (ref "IC4") (pin "38") (pinfunction "RD0/CPS8/COM3_38") (pintype "bidirectional"))
      (node (ref "RN1") (pin "7") (pinfunction "7_7") (pintype "passive"))
    )
    (net (code "59") (name "OUT7") (class "Default")
      (node (ref "IC2") (pin "7") (pinfunction "P$7_7") (pintype "input"))
      (node (ref "IC4") (pin "37") (pinfunction "RC3/SCL/SCK/SEG6_37") (pintype "bidirectional"))
      (node (ref "RN1") (pin "8") (pinfunction "8_8") (pintype "passive"))
    )
    (net (code "60") (name "OUT8") (class "Default")
      (node (ref "IC2") (pin "8") (pinfunction "P$8_8") (pintype "input"))
      (node (ref "IC4") (pin "36") (pinfunction "RC2/CCP1/P1A/SEG3_36") (pintype "bidirectional"))
      (node (ref "RN1") (pin "9") (pinfunction "9_9") (pintype "passive"))
    )
    (net (code "61") (name "OUT9") (class "Default")
      (node (ref "IC3") (pin "3") (pinfunction "P$3_3") (pintype "input"))
      (node (ref "IC4") (pin "30") (pinfunction "RA7/OSC1/CLKIN/SEG2_30") (pintype "bidirectional"))
      (node (ref "RN2") (pin "9") (pinfunction "9_9") (pintype "passive"))
    )
    (net (code "62") (name "OUT10") (class "Default")
      (node (ref "IC3") (pin "4") (pinfunction "P$4_4") (pintype "input"))
      (node (ref "IC4") (pin "27") (pinfunction "RE2/AN7/CCP5/SEG23_27") (pintype "bidirectional"))
      (node (ref "RN2") (pin "8") (pinfunction "8_8") (pintype "passive"))
    )
    (net (code "63") (name "OUT11") (class "Default")
      (node (ref "IC3") (pin "7") (pinfunction "P$7_7") (pintype "input"))
      (node (ref "IC4") (pin "26") (pinfunction "RE1/AN6/P3B/SEG22_26") (pintype "bidirectional"))
      (node (ref "RN2") (pin "7") (pinfunction "7_7") (pintype "passive"))
    )
    (net (code "64") (name "OUT12") (class "Default")
      (node (ref "IC3") (pin "8") (pinfunction "P$8_8") (pintype "input"))
      (node (ref "IC4") (pin "25") (pinfunction "RE0/AN5/CCP3/P3A/SEG21_25") (pintype "bidirectional"))
      (node (ref "RN2") (pin "6") (pinfunction "6_6") (pintype "passive"))
    )
    (net (code "65") (name "OUT13") (class "Default")
      (node (ref "IC4") (pin "24") (pinfunction "RA5/AN4/C2OUT/CPS7/SRNQ/~{SS}/VCAP/SEG5_24") (pintype "bidirectional"))
      (node (ref "IC5") (pin "3") (pinfunction "P$3_3") (pintype "input"))
      (node (ref "RN2") (pin "5") (pinfunction "5_5") (pintype "passive"))
    )
    (net (code "66") (name "OUT14") (class "Default")
      (node (ref "IC4") (pin "23") (pinfunction "RA4/C1OUT/CPS6/T0CKI/SRQ/SEG4_23") (pintype "bidirectional"))
      (node (ref "IC5") (pin "4") (pinfunction "P$4_4") (pintype "input"))
      (node (ref "RN2") (pin "4") (pinfunction "4_4") (pintype "passive"))
    )
    (net (code "67") (name "OUT15") (class "Default")
      (node (ref "IC4") (pin "22") (pinfunction "SEG15/VREF+/C1IN+/AN3/RA3_22") (pintype "bidirectional"))
      (node (ref "IC5") (pin "7") (pinfunction "P$7_7") (pintype "input"))
      (node (ref "RN2") (pin "3") (pinfunction "3_3") (pintype "passive"))
    )
    (net (code "68") (name "OUT16") (class "Default")
      (node (ref "IC4") (pin "21") (pinfunction "COM2/DACOUT/VREF-/C2IN+/AN2/RA2_21") (pintype "bidirectional"))
      (node (ref "IC5") (pin "8") (pinfunction "P$8_8") (pintype "input"))
      (node (ref "RN2") (pin "2") (pinfunction "2_2") (pintype "passive"))
    )
    (net (code "69") (name "PGC") (class "Default")
      (node (ref "IC4") (pin "16") (pinfunction "SEG14/ICDCLK/ICSPCLK/RB6_16") (pintype "bidirectional"))
      (node (ref "JP7") (pin "5") (pinfunction "5_5") (pintype "passive"))
    )
    (net (code "70") (name "PGD") (class "Default")
      (node (ref "IC4") (pin "17") (pinfunction "SEG13/ICDDAT/ICSPDAT/RB7_17") (pintype "bidirectional"))
      (node (ref "JP7") (pin "4") (pinfunction "4_4") (pintype "passive"))
    )
    (net (code "71") (name "RS0") (class "Default")
      (node (ref "IC4") (pin "8") (pinfunction "SEG0/INT/SRI/CPS0/AN12/RB0_8") (pintype "bidirectional"))
      (node (ref "S1") (pin "1") (pinfunction "1_1") (pintype "passive"))
    )
    (net (code "72") (name "RS1") (class "Default")
      (node (ref "IC4") (pin "9") (pinfunction "VLCD1/CPS1/C12IN3-/AN10/RB1_9") (pintype "bidirectional"))
      (node (ref "S1") (pin "2") (pinfunction "2_2") (pintype "passive"))
    )
    (net (code "73") (name "RS2") (class "Default")
      (node (ref "IC4") (pin "10") (pinfunction "VLCD2/CPS2/AN8/RB2_10") (pintype "bidirectional"))
      (node (ref "S2") (pin "1") (pinfunction "1_1") (pintype "passive"))
    )
    (net (code "74") (name "RS3") (class "Default")
      (node (ref "IC4") (pin "11") (pinfunction "VLCD3/P2A/CCP2/CPS3/C12IN2-/AN9/RB3_11") (pintype "bidirectional"))
      (node (ref "S2") (pin "2") (pinfunction "2_2") (pintype "passive"))
    )
    (net (code "75") (name "RS4") (class "Default")
      (node (ref "IC4") (pin "14") (pinfunction "COM0/CPS4/AN11/RB4_14") (pintype "bidirectional"))
      (node (ref "S2") (pin "4") (pinfunction "4_4") (pintype "passive"))
    )
    (net (code "76") (name "RS5") (class "Default")
      (node (ref "IC4") (pin "15") (pinfunction "COM1/T1G/P3A/CCP3/CPS5/AN13/RB5_15") (pintype "bidirectional"))
      (node (ref "S2") (pin "8") (pinfunction "8_8") (pintype "passive"))
    )
    (net (code "77") (name "RXD") (class "Default")
      (node (ref "JP6") (pin "3") (pinfunction "3_3") (pintype "passive"))
      (node (ref "R12") (pin "2") (pinfunction "2_2") (pintype "passive"))
    )
    (net (code "78") (name "STRUT_GND") (class "Default")
      (node (ref "C3") (pin "1") (pinfunction "1_1") (pintype "passive"))
      (node (ref "H1") (pin "B3,2") (pinfunction "MOUNT_B3,2") (pintype "passive"))
      (node (ref "H2") (pin "B3,2") (pinfunction "MOUNT_B3,2") (pintype "passive"))
      (node (ref "R5") (pin "2") (pinfunction "2_2") (pintype "passive"))
    )
    (net (code "79") (name "TEST") (class "Default")
      (node (ref "C16") (pin "1") (pinfunction "1_1") (pintype "passive"))
      (node (ref "IC4") (pin "5") (pinfunction "SEG20/P1D/CPS15/RD7_5") (pintype "bidirectional"))
      (node (ref "R28") (pin "2") (pinfunction "2_2") (pintype "passive"))
      (node (ref "S3") (pin "P$2") (pinfunction "P$2_P$2") (pintype "bidirectional"))
    )
    (net (code "80") (name "TXD") (class "Default")
      (node (ref "JP6") (pin "2") (pinfunction "2_2") (pintype "passive"))
      (node (ref "R13") (pin "1") (pinfunction "1_1") (pintype "passive"))
    )
    (net (code "81") (name "VPP") (class "Default")
      (node (ref "C10") (pin "1") (pinfunction "1_1") (pintype "passive"))
      (node (ref "IC4") (pin "18") (pinfunction "VPP/~{MCLR}/RE3_18") (pintype "input"))
      (node (ref "JP7") (pin "1") (pinfunction "1_1") (pintype "passive"))
      (node (ref "R19") (pin "2") (pinfunction "2_2") (pintype "passive"))
    )
    (net (code "82") (name "unconnected-(H3-MOUNT-PadB3,2)") (class "Default")
      (node (ref "H3") (pin "B3,2") (pinfunction "MOUNT_B3,2") (pintype "passive"))
    )
    (net (code "83") (name "unconnected-(H4-MOUNT-PadB3,2)") (class "Default")
      (node (ref "H4") (pin "B3,2") (pinfunction "MOUNT_B3,2") (pintype "passive"))
    )
    (net (code "84") (name "unconnected-(IC1-P$9-Pad9)") (class "Default")
      (node (ref "IC1") (pin "9") (pinfunction "P$9_9") (pintype "output"))
    )
    (net (code "85") (name "unconnected-(IC1-P$12-Pad12)") (class "Default")
      (node (ref "IC1") (pin "12") (pinfunction "P$12_12") (pintype "output"))
    )
    (net (code "86") (name "unconnected-(IC1-P$13-Pad13)") (class "Default")
      (node (ref "IC1") (pin "13") (pinfunction "P$13_13") (pintype "output"))
    )
    (net (code "87") (name "unconnected-(IC1-P$16-Pad16)") (class "Default")
      (node (ref "IC1") (pin "16") (pinfunction "P$16_16") (pintype "output"))
    )
    (net (code "88") (name "unconnected-(IC2-P$9-Pad9)") (class "Default")
      (node (ref "IC2") (pin "9") (pinfunction "P$9_9") (pintype "output"))
    )
    (net (code "89") (name "unconnected-(IC2-P$12-Pad12)") (class "Default")
      (node (ref "IC2") (pin "12") (pinfunction "P$12_12") (pintype "output"))
    )
    (net (code "90") (name "unconnected-(IC2-P$13-Pad13)") (class "Default")
      (node (ref "IC2") (pin "13") (pinfunction "P$13_13") (pintype "output"))
    )
    (net (code "91") (name "unconnected-(IC2-P$16-Pad16)") (class "Default")
      (node (ref "IC2") (pin "16") (pinfunction "P$16_16") (pintype "output"))
    )
    (net (code "92") (name "unconnected-(IC3-P$9-Pad9)") (class "Default")
      (node (ref "IC3") (pin "9") (pinfunction "P$9_9") (pintype "output"))
    )
    (net (code "93") (name "unconnected-(IC3-P$12-Pad12)") (class "Default")
      (node (ref "IC3") (pin "12") (pinfunction "P$12_12") (pintype "output"))
    )
    (net (code "94") (name "unconnected-(IC3-P$13-Pad13)") (class "Default")
      (node (ref "IC3") (pin "13") (pinfunction "P$13_13") (pintype "output"))
    )
    (net (code "95") (name "unconnected-(IC3-P$16-Pad16)") (class "Default")
      (node (ref "IC3") (pin "16") (pinfunction "P$16_16") (pintype "output"))
    )
    (net (code "96") (name "unconnected-(IC4-NC-Pad12)") (class "Default")
      (node (ref "IC4") (pin "12") (pinfunction "NC_12") (pintype "no_connect"))
    )
    (net (code "97") (name "unconnected-(IC4-NC-Pad13)") (class "Default")
      (node (ref "IC4") (pin "13") (pinfunction "NC_13") (pintype "no_connect"))
    )
    (net (code "98") (name "unconnected-(IC4-NC-Pad33)") (class "Default")
      (node (ref "IC4") (pin "33") (pinfunction "NC_33") (pintype "no_connect"))
    )
    (net (code "99") (name "unconnected-(IC4-NC-Pad34)") (class "Default")
      (node (ref "IC4") (pin "34") (pinfunction "NC_34") (pintype "no_connect"))
    )
    (net (code "100") (name "unconnected-(IC4-SEG7{slash}C12IN1-{slash}AN1{slash}RA1-Pad20)") (class "Default")
      (node (ref "IC4") (pin "20") (pinfunction "SEG7/C12IN1-/AN1/RA1_20") (pintype "bidirectional"))
    )
    (net (code "101") (name "unconnected-(IC5-P$9-Pad9)") (class "Default")
      (node (ref "IC5") (pin "9") (pinfunction "P$9_9") (pintype "output"))
    )
    (net (code "102") (name "unconnected-(IC5-P$12-Pad12)") (class "Default")
      (node (ref "IC5") (pin "12") (pinfunction "P$12_12") (pintype "output"))
    )
    (net (code "103") (name "unconnected-(IC5-P$13-Pad13)") (class "Default")
      (node (ref "IC5") (pin "13") (pinfunction "P$13_13") (pintype "output"))
    )
    (net (code "104") (name "unconnected-(IC5-P$16-Pad16)") (class "Default")
      (node (ref "IC5") (pin "16") (pinfunction "P$16_16") (pintype "output"))
    )
    (net (code "105") (name "unconnected-(OK1-BAS-Pad6)") (class "Default")
      (node (ref "OK1") (pin "6") (pinfunction "BAS_6") (pintype "passive"))
    )
  )
)
